# Clock_generator.net
KiCad netlist of a schematic drawn in EAGLE
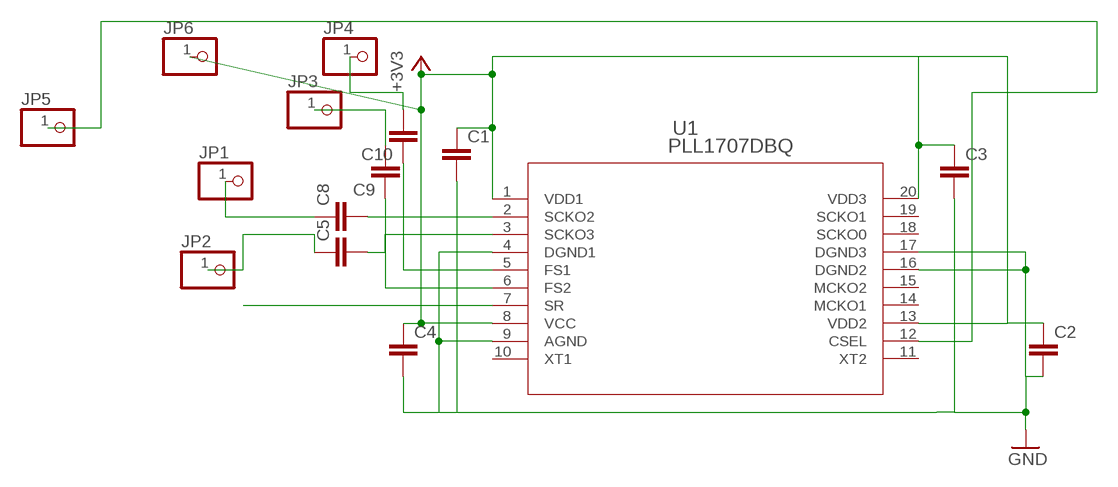
[diagram p0: schematic, sheet 1]

(export (version "E")
  (design (tool "Eeschema 10.0.6"))
  (components
    (comp (ref "C1")
      (value "C-EUC0805K")
      (footprint "eagle-import:C0805K")
      (libsource (lib "eagle-import") (part "C-EUC0805K"))
    )
    (comp (ref "C2")
      (value "C-EUC0805K")
      (footprint "eagle-import:C0805K")
      (libsource (lib "eagle-import") (part "C-EUC0805K"))
    )
    (comp (ref "C3")
      (value "C-EUC0805K")
      (footprint "eagle-import:C0805K")
      (libsource (lib "eagle-import") (part "C-EUC0805K"))
    )
    (comp (ref "C4")
      (value "C-EUC0805K")
      (footprint "eagle-import:C0805K")
      (libsource (lib "eagle-import") (part "C-EUC0805K"))
    )
    (comp (ref "C5")
      (value "C-EUC0805K")
      (footprint "eagle-import:C0805K")
      (libsource (lib "eagle-import") (part "C-EUC0805K"))
    )
    (comp (ref "C8")
      (value "C-EUC0805K")
      (footprint "eagle-import:C0805K")
      (libsource (lib "eagle-import") (part "C-EUC0805K"))
    )
    (comp (ref "C9")
      (value "C-EUC0805K")
      (footprint "eagle-import:C0805K")
      (libsource (lib "eagle-import") (part "C-EUC0805K"))
    )
    (comp (ref "C10")
      (value "C-EUC0805K")
      (footprint "eagle-import:C0805K")
      (libsource (lib "eagle-import") (part "C-EUC0805K"))
    )
    (comp (ref "JP1")
      (value "PINHD-1X1")
      (footprint "eagle-import:1X01")
      (libsource (lib "eagle-import") (part "PINHD-1X1"))
    )
    (comp (ref "JP2")
      (value "PINHD-1X1")
      (footprint "eagle-import:1X01")
      (libsource (lib "eagle-import") (part "PINHD-1X1"))
    )
    (comp (ref "JP3")
      (value "PINHD-1X1")
      (footprint "eagle-import:1X01")
      (libsource (lib "eagle-import") (part "PINHD-1X1"))
    )
    (comp (ref "JP4")
      (value "PINHD-1X1")
      (footprint "eagle-import:1X01")
      (libsource (lib "eagle-import") (part "PINHD-1X1"))
    )
    (comp (ref "JP5")
      (value "PINHD-1X1")
      (footprint "eagle-import:1X01")
      (libsource (lib "eagle-import") (part "PINHD-1X1"))
    )
    (comp (ref "JP6")
      (value "PINHD-1X1")
      (footprint "eagle-import:1X01")
      (libsource (lib "eagle-import") (part "PINHD-1X1"))
    )
    (comp (ref "U1")
      (value "PLL1707DBQ")
      (footprint "eagle-import:DBQ20")
      (fields
        (field (name "GENERIC_PART_NUMBER") "PLL1707")
        (field (name "MANUFACTURER") "Texas Instruments")
      )
      (libsource (lib "eagle-import") (part "PLL1707DBQ"))
    )
  )
  (nets
    (net (code "1") (name "+3V3") (class "Default")
      (node (ref "C1") (pin "1") (pinfunction "1_1") (pintype "passive"))
      (node (ref "C2") (pin "1") (pinfunction "1_1") (pintype "passive"))
      (node (ref "C3") (pin "1") (pinfunction "1_1") (pintype "passive"))
      (node (ref "C4") (pin "1") (pinfunction "1_1") (pintype "passive"))
      (node (ref "JP6") (pin "1") (pinfunction "1_1") (pintype "passive"))
      (node (ref "U1") (pin "1") (pinfunction "VDD1_1") (pintype "power_in"))
      (node (ref "U1") (pin "13") (pinfunction "VDD2_13") (pintype "power_in"))
      (node (ref "U1") (pin "20") (pinfunction "VDD3_20") (pintype "power_in"))
      (node (ref "U1") (pin "8") (pinfunction "VCC_8") (pintype "power_in"))
    )
    (net (code "2") (name "GND") (class "Default")
      (node (ref "C1") (pin "2") (pinfunction "2_2") (pintype "passive"))
      (node (ref "C2") (pin "2") (pinfunction "2_2") (pintype "passive"))
      (node (ref "C3") (pin "2") (pinfunction "2_2") (pintype "passive"))
      (node (ref "C4") (pin "2") (pinfunction "2_2") (pintype "passive"))
      (node (ref "U1") (pin "16") (pinfunction "DGND2_16") (pintype "power_in"))
      (node (ref "U1") (pin "17") (pinfunction "DGND3_17") (pintype "power_in"))
      (node (ref "U1") (pin "4") (pinfunction "DGND1_4") (pintype "power_in"))
      (node (ref "U1") (pin "9") (pinfunction "AGND_9") (pintype "power_in"))
    )
    (net (code "3") (name "Net-(C5-Pad1)") (class "Default")
      (node (ref "C5") (pin "1") (pinfunction "1_1") (pintype "passive"))
      (node (ref "JP2") (pin "1") (pinfunction "1_1") (pintype "passive"))
    )
    (net (code "4") (name "Net-(C8-Pad1)") (class "Default")
      (node (ref "C8") (pin "1") (pinfunction "1_1") (pintype "passive"))
      (node (ref "JP1") (pin "1") (pinfunction "1_1") (pintype "passive"))
    )
    (net (code "5") (name "Net-(C9-Pad2)") (class "Default")
      (node (ref "C9") (pin "2") (pinfunction "2_2") (pintype "passive"))
      (node (ref "JP3") (pin "1") (pinfunction "1_1") (pintype "passive"))
    )
    (net (code "6") (name "Net-(C10-Pad2)") (class "Default")
      (node (ref "C10") (pin "2") (pinfunction "2_2") (pintype "passive"))
      (node (ref "JP4") (pin "1") (pinfunction "1_1") (pintype "passive"))
    )
    (net (code "7") (name "Net-(U1-CSEL)") (class "Default")
      (node (ref "JP5") (pin "1") (pinfunction "1_1") (pintype "passive"))
      (node (ref "U1") (pin "12") (pinfunction "CSEL_12") (pintype "input"))
    )
    (net (code "8") (name "Net-(U1-FS1)") (class "Default")
      (node (ref "C10") (pin "1") (pinfunction "1_1") (pintype "passive"))
      (node (ref "U1") (pin "5") (pinfunction "FS1_5") (pintype "input"))
    )
    (net (code "9") (name "Net-(U1-FS2)") (class "Default")
      (node (ref "C9") (pin "1") (pinfunction "1_1") (pintype "passive"))
      (node (ref "U1") (pin "6") (pinfunction "FS2_6") (pintype "input"))
    )
    (net (code "10") (name "Net-(U1-SCKO2)") (class "Default")
      (node (ref "C8") (pin "2") (pinfunction "2_2") (pintype "passive"))
      (node (ref "U1") (pin "2") (pinfunction "SCKO2_2") (pintype "output"))
    )
    (net (code "11") (name "Net-(U1-SCKO3)") (class "Default")
      (node (ref "C5") (pin "2") (pinfunction "2_2") (pintype "passive"))
      (node (ref "U1") (pin "3") (pinfunction "SCKO3_3") (pintype "output"))
    )
    (net (code "12") (name "unconnected-(U1-MCKO1-Pad14)") (class "Default")
      (node (ref "U1") (pin "14") (pinfunction "MCKO1_14") (pintype "output"))
    )
    (net (code "13") (name "unconnected-(U1-MCKO2-Pad15)") (class "Default")
      (node (ref "U1") (pin "15") (pinfunction "MCKO2_15") (pintype "output"))
    )
    (net (code "14") (name "unconnected-(U1-SCKO0-Pad18)") (class "Default")
      (node (ref "U1") (pin "18") (pinfunction "SCKO0_18") (pintype "output"))
    )
    (net (code "15") (name "unconnected-(U1-SCKO1-Pad19)") (class "Default")
      (node (ref "U1") (pin "19") (pinfunction "SCKO1_19") (pintype "output"))
    )
    (net (code "16") (name "unconnected-(U1-SR-Pad7)") (class "Default")
      (node (ref "U1") (pin "7") (pinfunction "SR_7") (pintype "input"))
    )
    (net (code "17") (name "unconnected-(U1-XT1-Pad10)") (class "Default")
      (node (ref "U1") (pin "10") (pinfunction "XT1_10") (pintype "input"))
    )
    (net (code "18") (name "unconnected-(U1-XT2-Pad11)") (class "Default")
      (node (ref "U1") (pin "11") (pinfunction "XT2_11") (pintype "output"))
    )
  )
)
